# Simon_Game_Rev_G.net
KiCad netlist of a schematic drawn in EAGLE
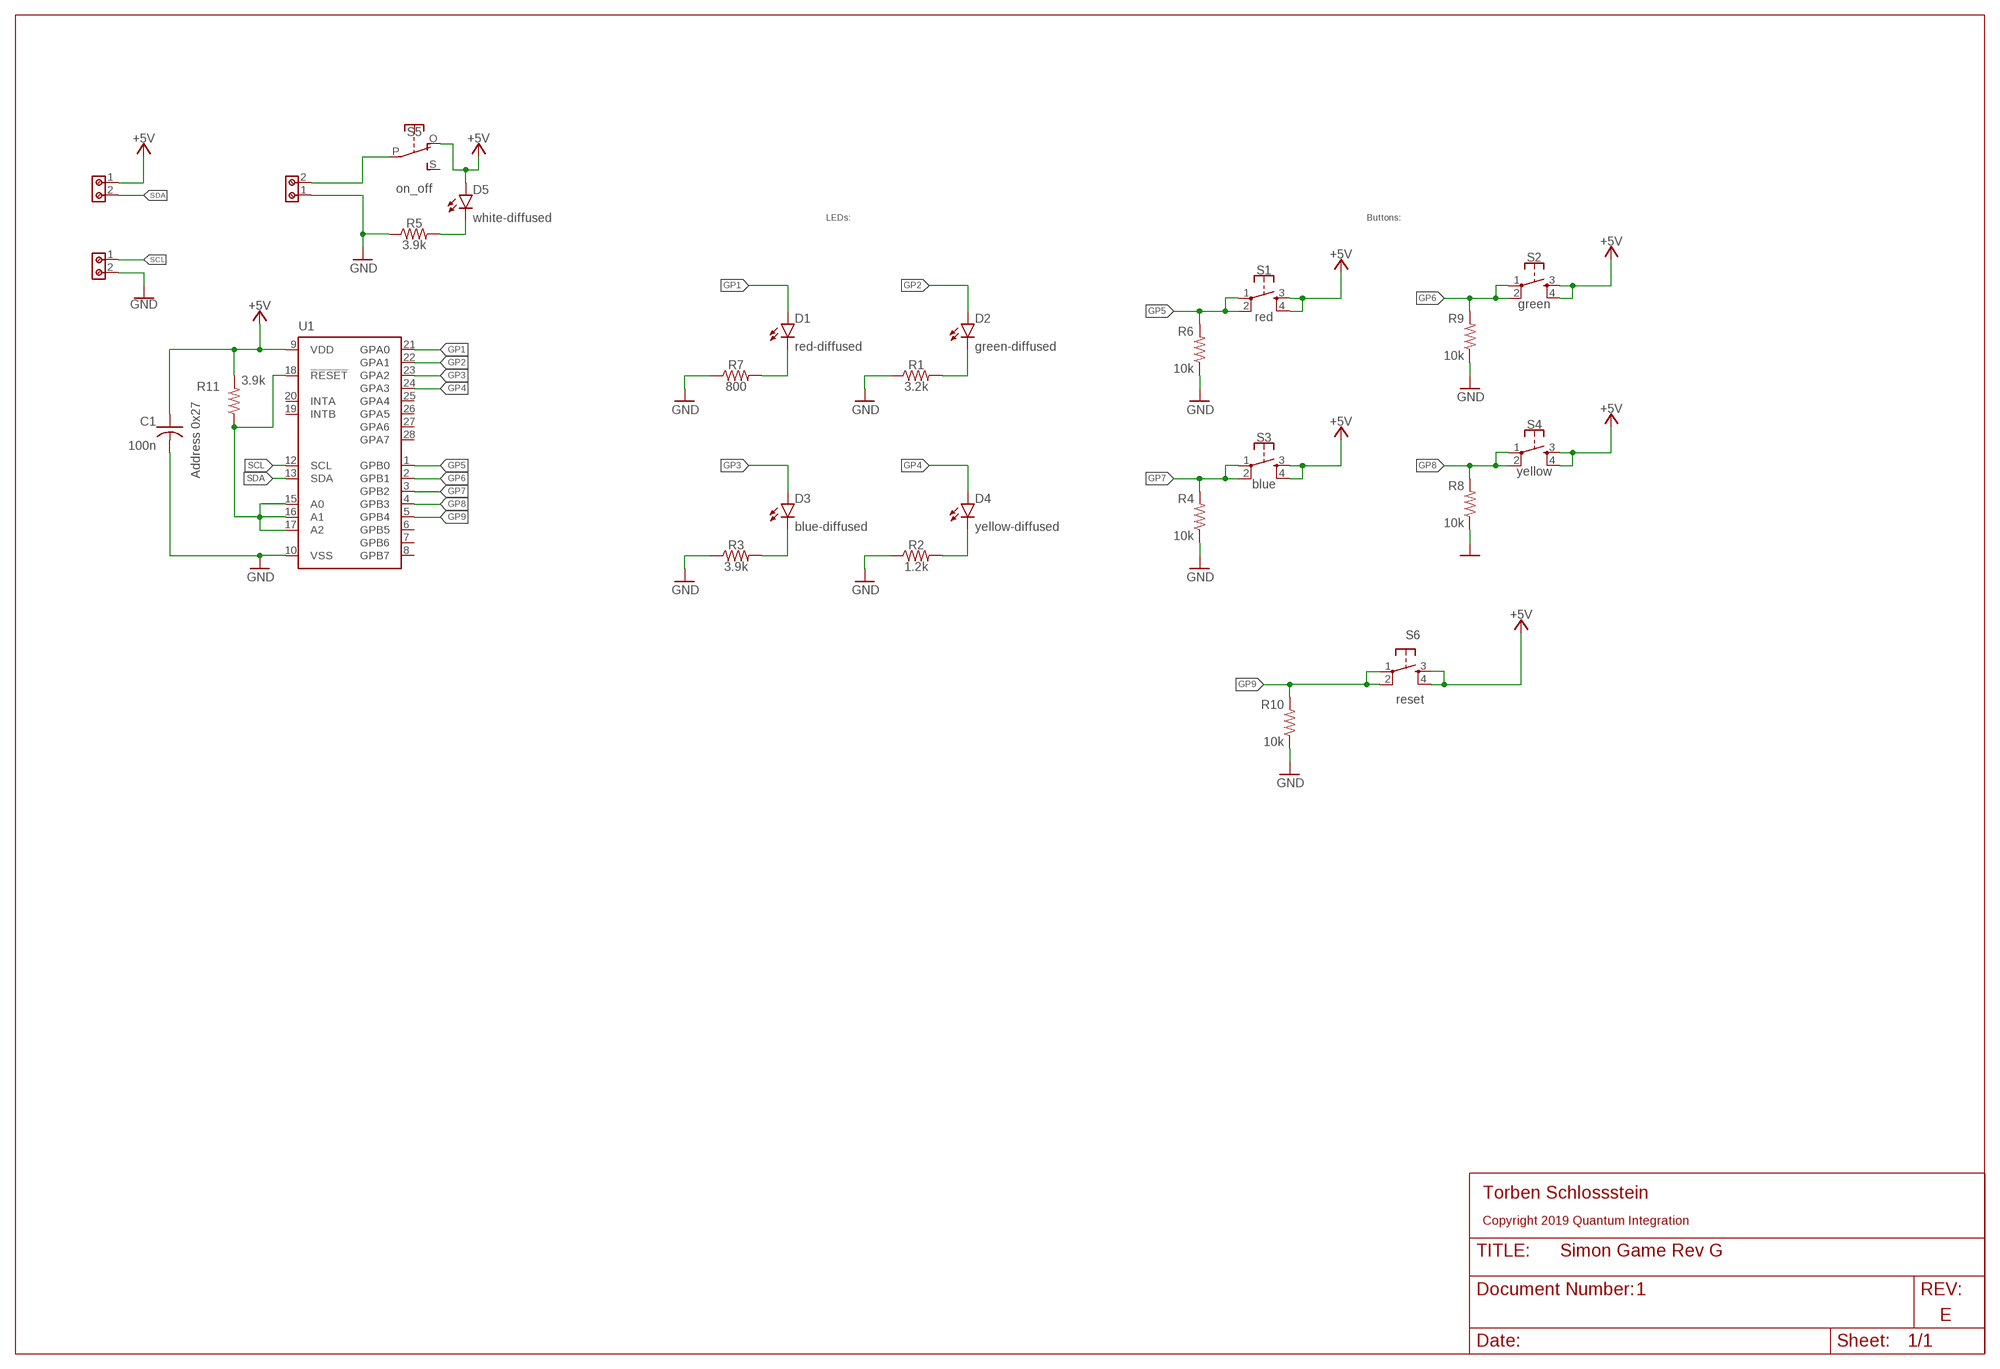
[diagram p0: schematic, sheet 1]

(export (version "E")
  (design (tool "Eeschema 10.0.6"))
  (components
    (comp (ref "C1")
      (value "100n")
      (footprint "eagle-import:C050-024X044")
      (libsource (lib "eagle-import") (part "THT-CER-CAPACITOR"))
    )
    (comp (ref "D1")
      (value "red-diffused")
      (footprint "eagle-import:LED5MM")
      (libsource (lib "eagle-import") (part "LED"))
    )
    (comp (ref "D2")
      (value "green-diffused")
      (footprint "eagle-import:LED5MM")
      (libsource (lib "eagle-import") (part "LED"))
    )
    (comp (ref "D3")
      (value "blue-diffused")
      (footprint "eagle-import:LED5MM")
      (libsource (lib "eagle-import") (part "LED"))
    )
    (comp (ref "D4")
      (value "yellow-diffused")
      (footprint "eagle-import:LED5MM")
      (libsource (lib "eagle-import") (part "LED"))
    )
    (comp (ref "D5")
      (value "white-diffused")
      (footprint "eagle-import:LED5MM")
      (libsource (lib "eagle-import") (part "LED"))
    )
    (comp (ref "J1")
      (value "691214110002")
      (footprint "eagle-import:691214110002")
      (libsource (lib "eagle-import") (part "691214110002"))
    )
    (comp (ref "J2")
      (value "691214110002")
      (footprint "eagle-import:691214110002")
      (libsource (lib "eagle-import") (part "691214110002"))
    )
    (comp (ref "J3")
      (value "691214110002")
      (footprint "eagle-import:691214110002")
      (libsource (lib "eagle-import") (part "691214110002"))
    )
    (comp (ref "R1")
      (value "3.2k")
      (footprint "eagle-import:0207_10")
      (libsource (lib "eagle-import") (part "RESISTOR"))
    )
    (comp (ref "R2")
      (value "1.2k")
      (footprint "eagle-import:0207_10")
      (libsource (lib "eagle-import") (part "RESISTOR"))
    )
    (comp (ref "R3")
      (value "3.9k")
      (footprint "eagle-import:0207_10")
      (libsource (lib "eagle-import") (part "RESISTOR"))
    )
    (comp (ref "R4")
      (value "10k")
      (footprint "eagle-import:0207_10")
      (libsource (lib "eagle-import") (part "RESISTOR"))
    )
    (comp (ref "R5")
      (value "3.9k")
      (footprint "eagle-import:0207_10")
      (libsource (lib "eagle-import") (part "RESISTOR"))
    )
    (comp (ref "R6")
      (value "10k")
      (footprint "eagle-import:0207_10")
      (libsource (lib "eagle-import") (part "RESISTOR"))
    )
    (comp (ref "R7")
      (value "800")
      (footprint "eagle-import:0207_10")
      (libsource (lib "eagle-import") (part "RESISTOR"))
    )
    (comp (ref "R8")
      (value "10k")
      (footprint "eagle-import:0207_10")
      (libsource (lib "eagle-import") (part "RESISTOR"))
    )
    (comp (ref "R9")
      (value "10k")
      (footprint "eagle-import:0207_10")
      (libsource (lib "eagle-import") (part "RESISTOR"))
    )
    (comp (ref "R10")
      (value "10k")
      (footprint "eagle-import:0207_10")
      (libsource (lib "eagle-import") (part "RESISTOR"))
    )
    (comp (ref "R11")
      (value "3.9k")
      (footprint "eagle-import:0207_10")
      (libsource (lib "eagle-import") (part "RESISTOR"))
    )
    (comp (ref "S1")
      (value "red")
      (footprint "eagle-import:B3F-40XX")
      (libsource (lib "eagle-import") (part "TACTILE-BUTTON40XX"))
    )
    (comp (ref "S2")
      (value "green")
      (footprint "eagle-import:B3F-40XX")
      (libsource (lib "eagle-import") (part "TACTILE-BUTTON40XX"))
    )
    (comp (ref "S3")
      (value "blue")
      (footprint "eagle-import:B3F-40XX")
      (libsource (lib "eagle-import") (part "TACTILE-BUTTON40XX"))
    )
    (comp (ref "S4")
      (value "yellow")
      (footprint "eagle-import:B3F-40XX")
      (libsource (lib "eagle-import") (part "TACTILE-BUTTON40XX"))
    )
    (comp (ref "S5")
      (value "on_off")
      (footprint "eagle-import:EG1270-90")
      (libsource (lib "eagle-import") (part "SLIDE-SWITCHSIDE"))
    )
    (comp (ref "S6")
      (value "reset")
      (footprint "eagle-import:B3F-10XX")
      (libsource (lib "eagle-import") (part "TACTILE-BUTTON10XX"))
    )
    (comp (ref "U1")
      (value "MCP23017")
      (footprint "eagle-import:DIL28-3")
      (libsource (lib "eagle-import") (part "MCP23017"))
    )
  )
  (nets
    (net (code "1") (name "+5V") (class "Default")
      (node (ref "C1") (pin "1") (pinfunction "1_1") (pintype "passive"))
      (node (ref "D5") (pin "A") (pinfunction "A_A") (pintype "passive"))
      (node (ref "J2") (pin "1") (pinfunction "1_1") (pintype "passive"))
      (node (ref "R11") (pin "2") (pinfunction "2_2") (pintype "passive"))
      (node (ref "S1") (pin "3") (pinfunction "S_3") (pintype "passive"))
      (node (ref "S1") (pin "4") (pinfunction "S1_4") (pintype "passive"))
      (node (ref "S2") (pin "3") (pinfunction "S_3") (pintype "passive"))
      (node (ref "S2") (pin "4") (pinfunction "S1_4") (pintype "passive"))
      (node (ref "S3") (pin "3") (pinfunction "S_3") (pintype "passive"))
      (node (ref "S3") (pin "4") (pinfunction "S1_4") (pintype "passive"))
      (node (ref "S4") (pin "3") (pinfunction "S_3") (pintype "passive"))
      (node (ref "S4") (pin "4") (pinfunction "S1_4") (pintype "passive"))
      (node (ref "S5") (pin "O") (pinfunction "O_O") (pintype "passive"))
      (node (ref "S6") (pin "3") (pinfunction "S_3") (pintype "passive"))
      (node (ref "S6") (pin "4") (pinfunction "S1_4") (pintype "passive"))
      (node (ref "U1") (pin "9") (pinfunction "VDD_9") (pintype "power_in"))
    )
    (net (code "2") (name "GND") (class "Default")
      (node (ref "C1") (pin "2") (pinfunction "2_2") (pintype "passive"))
      (node (ref "J1") (pin "1") (pinfunction "1_1") (pintype "passive"))
      (node (ref "J3") (pin "2") (pinfunction "2_2") (pintype "passive"))
      (node (ref "R1") (pin "1") (pinfunction "1_1") (pintype "passive"))
      (node (ref "R10") (pin "1") (pinfunction "1_1") (pintype "passive"))
      (node (ref "R2") (pin "1") (pinfunction "1_1") (pintype "passive"))
      (node (ref "R3") (pin "1") (pinfunction "1_1") (pintype "passive"))
      (node (ref "R4") (pin "1") (pinfunction "1_1") (pintype "passive"))
      (node (ref "R5") (pin "1") (pinfunction "1_1") (pintype "passive"))
      (node (ref "R6") (pin "1") (pinfunction "1_1") (pintype "passive"))
      (node (ref "R7") (pin "1") (pinfunction "1_1") (pintype "passive"))
      (node (ref "R8") (pin "1") (pinfunction "1_1") (pintype "passive"))
      (node (ref "R9") (pin "1") (pinfunction "1_1") (pintype "passive"))
      (node (ref "U1") (pin "10") (pinfunction "VSS_10") (pintype "power_in"))
    )
    (net (code "3") (name "GP1") (class "Default")
      (node (ref "D1") (pin "A") (pinfunction "A_A") (pintype "passive"))
      (node (ref "U1") (pin "21") (pinfunction "GPA0_21") (pintype "bidirectional"))
    )
    (net (code "4") (name "GP2") (class "Default")
      (node (ref "D2") (pin "A") (pinfunction "A_A") (pintype "passive"))
      (node (ref "U1") (pin "22") (pinfunction "GPA1_22") (pintype "bidirectional"))
    )
    (net (code "5") (name "GP3") (class "Default")
      (node (ref "D3") (pin "A") (pinfunction "A_A") (pintype "passive"))
      (node (ref "U1") (pin "23") (pinfunction "GPA2_23") (pintype "bidirectional"))
    )
    (net (code "6") (name "GP4") (class "Default")
      (node (ref "D4") (pin "A") (pinfunction "A_A") (pintype "passive"))
      (node (ref "U1") (pin "24") (pinfunction "GPA3_24") (pintype "bidirectional"))
    )
    (net (code "7") (name "GP5") (class "Default")
      (node (ref "R6") (pin "2") (pinfunction "2_2") (pintype "passive"))
      (node (ref "S1") (pin "1") (pinfunction "P_1") (pintype "passive"))
      (node (ref "S1") (pin "2") (pinfunction "P1_2") (pintype "passive"))
      (node (ref "U1") (pin "1") (pinfunction "GPB0_1") (pintype "bidirectional"))
    )
    (net (code "8") (name "GP6") (class "Default")
      (node (ref "R9") (pin "2") (pinfunction "2_2") (pintype "passive"))
      (node (ref "S2") (pin "1") (pinfunction "P_1") (pintype "passive"))
      (node (ref "S2") (pin "2") (pinfunction "P1_2") (pintype "passive"))
      (node (ref "U1") (pin "2") (pinfunction "GPB1_2") (pintype "bidirectional"))
    )
    (net (code "9") (name "GP7") (class "Default")
      (node (ref "R4") (pin "2") (pinfunction "2_2") (pintype "passive"))
      (node (ref "S3") (pin "1") (pinfunction "P_1") (pintype "passive"))
      (node (ref "S3") (pin "2") (pinfunction "P1_2") (pintype "passive"))
      (node (ref "U1") (pin "3") (pinfunction "GPB2_3") (pintype "bidirectional"))
    )
    (net (code "10") (name "GP8") (class "Default")
      (node (ref "R8") (pin "2") (pinfunction "2_2") (pintype "passive"))
      (node (ref "S4") (pin "1") (pinfunction "P_1") (pintype "passive"))
      (node (ref "S4") (pin "2") (pinfunction "P1_2") (pintype "passive"))
      (node (ref "U1") (pin "4") (pinfunction "GPB3_4") (pintype "bidirectional"))
    )
    (net (code "11") (name "GP9") (class "Default")
      (node (ref "R10") (pin "2") (pinfunction "2_2") (pintype "passive"))
      (node (ref "S6") (pin "1") (pinfunction "P_1") (pintype "passive"))
      (node (ref "S6") (pin "2") (pinfunction "P1_2") (pintype "passive"))
      (node (ref "U1") (pin "5") (pinfunction "GPB4_5") (pintype "bidirectional"))
    )
    (net (code "12") (name "Net-(D1-C)") (class "Default")
      (node (ref "D1") (pin "K") (pinfunction "C_K") (pintype "passive"))
      (node (ref "R7") (pin "2") (pinfunction "2_2") (pintype "passive"))
    )
    (net (code "13") (name "Net-(D2-C)") (class "Default")
      (node (ref "D2") (pin "K") (pinfunction "C_K") (pintype "passive"))
      (node (ref "R1") (pin "2") (pinfunction "2_2") (pintype "passive"))
    )
    (net (code "14") (name "Net-(D3-C)") (class "Default")
      (node (ref "D3") (pin "K") (pinfunction "C_K") (pintype "passive"))
      (node (ref "R3") (pin "2") (pinfunction "2_2") (pintype "passive"))
    )
    (net (code "15") (name "Net-(D4-C)") (class "Default")
      (node (ref "D4") (pin "K") (pinfunction "C_K") (pintype "passive"))
      (node (ref "R2") (pin "2") (pinfunction "2_2") (pintype "passive"))
    )
    (net (code "16") (name "Net-(D5-C)") (class "Default")
      (node (ref "D5") (pin "K") (pinfunction "C_K") (pintype "passive"))
      (node (ref "R5") (pin "2") (pinfunction "2_2") (pintype "passive"))
    )
    (net (code "17") (name "Net-(J1-Pad2)") (class "Default")
      (node (ref "J1") (pin "2") (pinfunction "2_2") (pintype "passive"))
      (node (ref "S5") (pin "P") (pinfunction "P_P") (pintype "passive"))
    )
    (net (code "18") (name "Net-(U1-A0)") (class "Default")
      (node (ref "R11") (pin "1") (pinfunction "1_1") (pintype "passive"))
      (node (ref "U1") (pin "15") (pinfunction "A0_15") (pintype "input"))
      (node (ref "U1") (pin "16") (pinfunction "A1_16") (pintype "input"))
      (node (ref "U1") (pin "17") (pinfunction "A2_17") (pintype "input"))
      (node (ref "U1") (pin "18") (pinfunction "~{RESET}_18") (pintype "input"))
    )
    (net (code "19") (name "SCL") (class "Default")
      (node (ref "J3") (pin "1") (pinfunction "1_1") (pintype "passive"))
      (node (ref "U1") (pin "12") (pinfunction "SCL_12") (pintype "input"))
    )
    (net (code "20") (name "SDA") (class "Default")
      (node (ref "J2") (pin "2") (pinfunction "2_2") (pintype "passive"))
      (node (ref "U1") (pin "13") (pinfunction "SDA_13") (pintype "bidirectional"))
    )
    (net (code "21") (name "unconnected-(S5-PadS)") (class "Default")
      (node (ref "S5") (pin "S") (pinfunction "S_S") (pintype "passive"))
    )
    (net (code "22") (name "unconnected-(U1-GPA4-Pad25)") (class "Default")
      (node (ref "U1") (pin "25") (pinfunction "GPA4_25") (pintype "bidirectional"))
    )
    (net (code "23") (name "unconnected-(U1-GPA5-Pad26)") (class "Default")
      (node (ref "U1") (pin "26") (pinfunction "GPA5_26") (pintype "bidirectional"))
    )
    (net (code "24") (name "unconnected-(U1-GPA6-Pad27)") (class "Default")
      (node (ref "U1") (pin "27") (pinfunction "GPA6_27") (pintype "bidirectional"))
    )
    (net (code "25") (name "unconnected-(U1-GPA7-Pad28)") (class "Default")
      (node (ref "U1") (pin "28") (pinfunction "GPA7_28") (pintype "bidirectional"))
    )
    (net (code "26") (name "unconnected-(U1-GPB5-Pad6)") (class "Default")
      (node (ref "U1") (pin "6") (pinfunction "GPB5_6") (pintype "bidirectional"))
    )
    (net (code "27") (name "unconnected-(U1-GPB6-Pad7)") (class "Default")
      (node (ref "U1") (pin "7") (pinfunction "GPB6_7") (pintype "bidirectional"))
    )
    (net (code "28") (name "unconnected-(U1-GPB7-Pad8)") (class "Default")
      (node (ref "U1") (pin "8") (pinfunction "GPB7_8") (pintype "bidirectional"))
    )
    (net (code "29") (name "unconnected-(U1-INTA-Pad20)") (class "Default")
      (node (ref "U1") (pin "20") (pinfunction "INTA_20") (pintype "output"))
    )
    (net (code "30") (name "unconnected-(U1-INTB-Pad19)") (class "Default")
      (node (ref "U1") (pin "19") (pinfunction "INTB_19") (pintype "output"))
    )
  )
)
